# DSO_CPLD.net
KiCad netlist of a schematic drawn in Altium Designer
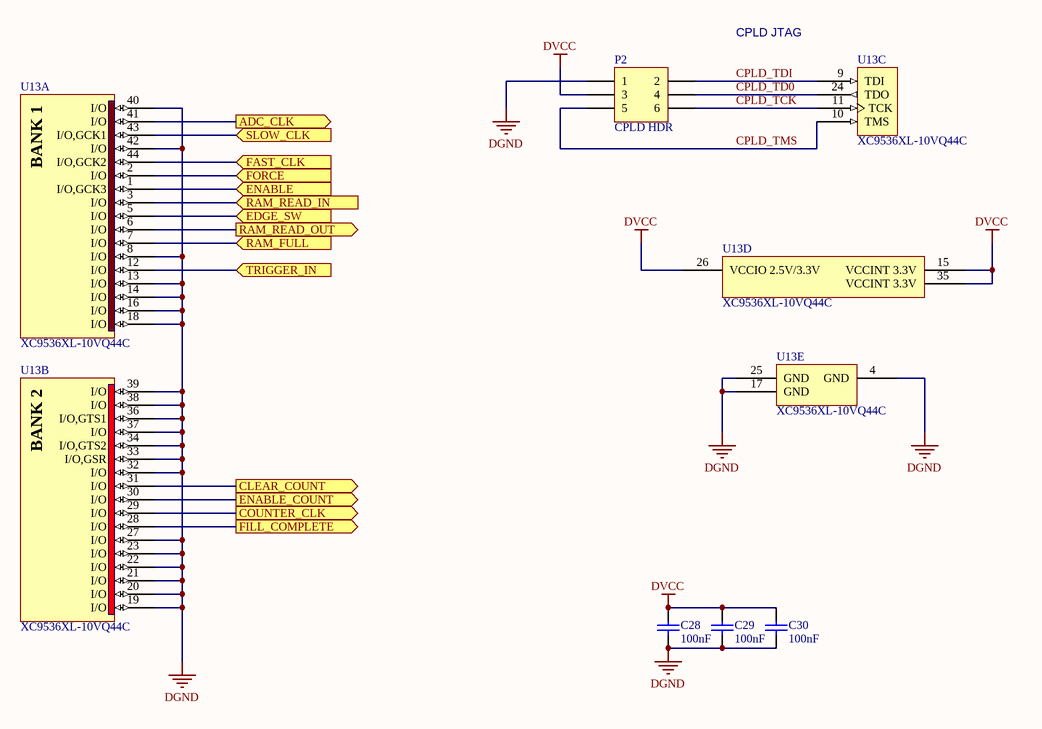
[diagram p0: DSO_CPLD.SchDoc]

(export (version "E")
  (design (tool "Eeschema 10.0.6"))
  (components
    (comp (ref "C28")
      (value "100nF")
      (footprint "0805C")
      (description "Capacitor")
      (fields (field (name "REVIEWED BY") "RM - 2018/08/05"))
      (libsource (lib "DSO") (part "C"))
    )
    (comp (ref "C29")
      (value "100nF")
      (footprint "0805C")
      (description "Capacitor")
      (fields (field (name "REVIEWED BY") "RM - 2018/08/05"))
      (libsource (lib "DSO") (part "C"))
    )
    (comp (ref "C30")
      (value "100nF")
      (footprint "0805C")
      (description "Capacitor")
      (fields (field (name "REVIEWED BY") "RM - 2018/08/05"))
      (libsource (lib "DSO") (part "C"))
    )
    (comp (ref "P2")
      (value "CPLD HDR")
      (footprint "HDR3x2")
      (description "Header, 5-Pin")
      (fields (field (name "REVIEWED BY") "RM - 2018/08/05"))
      (libsource (lib "DSO") (part "Header 3x2"))
    )
    (comp (ref "U13")
      (value "XC9536XL-10VQ44C")
      (footprint "VQ44_L")
      (fields (field (name "REVIEWED BY") "RM - 2018/08/05"))
      (libsource (lib "DSO") (part "XC9536XL-10VQG44C"))
    )
  )
  (nets
    (net (code "1") (name "/ADC_CLK") (class "Default")
      (node (ref "U13") (pin "41") (pinfunction "I/O_41") (pintype "bidirectional"))
    )
    (net (code "2") (name "/CLEAR_COUNT") (class "Default")
      (node (ref "U13") (pin "31") (pinfunction "I/O_31") (pintype "bidirectional"))
    )
    (net (code "3") (name "/COUNTER_CLK") (class "Default")
      (node (ref "U13") (pin "29") (pinfunction "I/O_29") (pintype "bidirectional"))
    )
    (net (code "4") (name "/CPLD_TCK") (class "Default")
      (node (ref "P2") (pin "6") (pinfunction "6_6") (pintype "passive"))
      (node (ref "U13") (pin "11") (pinfunction "TCK_11") (pintype "input"))
    )
    (net (code "5") (name "/CPLD_TD0") (class "Default")
      (node (ref "P2") (pin "4") (pinfunction "4_4") (pintype "passive"))
      (node (ref "U13") (pin "24") (pinfunction "TDO_24") (pintype "output"))
    )
    (net (code "6") (name "/CPLD_TDI") (class "Default")
      (node (ref "P2") (pin "2") (pinfunction "2_2") (pintype "passive"))
      (node (ref "U13") (pin "9") (pinfunction "TDI_9") (pintype "input"))
    )
    (net (code "7") (name "/CPLD_TMS") (class "Default")
      (node (ref "P2") (pin "5") (pinfunction "5_5") (pintype "passive"))
      (node (ref "U13") (pin "10") (pinfunction "TMS_10") (pintype "input"))
    )
    (net (code "8") (name "/EDGE_SW") (class "Default")
      (node (ref "U13") (pin "5") (pinfunction "I/O_5") (pintype "bidirectional"))
    )
    (net (code "9") (name "/ENABLE") (class "Default")
      (node (ref "U13") (pin "1") (pinfunction "I/O,GCK3_1") (pintype "bidirectional"))
    )
    (net (code "10") (name "/ENABLE_COUNT") (class "Default")
      (node (ref "U13") (pin "30") (pinfunction "I/O_30") (pintype "bidirectional"))
    )
    (net (code "11") (name "/FAST_CLK") (class "Default")
      (node (ref "U13") (pin "44") (pinfunction "I/O,GCK2_44") (pintype "bidirectional"))
    )
    (net (code "12") (name "/FILL_COMPLETE") (class "Default")
      (node (ref "U13") (pin "28") (pinfunction "I/O_28") (pintype "bidirectional"))
    )
    (net (code "13") (name "/FORCE") (class "Default")
      (node (ref "U13") (pin "2") (pinfunction "I/O_2") (pintype "bidirectional"))
    )
    (net (code "14") (name "/RAM_FULL") (class "Default")
      (node (ref "U13") (pin "7") (pinfunction "I/O_7") (pintype "bidirectional"))
    )
    (net (code "15") (name "/RAM_READ_IN") (class "Default")
      (node (ref "U13") (pin "3") (pinfunction "I/O_3") (pintype "bidirectional"))
    )
    (net (code "16") (name "/RAM_READ_OUT") (class "Default")
      (node (ref "U13") (pin "6") (pinfunction "I/O_6") (pintype "bidirectional"))
    )
    (net (code "17") (name "/SLOW_CLK") (class "Default")
      (node (ref "U13") (pin "43") (pinfunction "I/O,GCK1_43") (pintype "bidirectional"))
    )
    (net (code "18") (name "/TRIGGER_IN") (class "Default")
      (node (ref "U13") (pin "12") (pinfunction "I/O_12") (pintype "bidirectional"))
    )
    (net (code "19") (name "DGND") (class "Default")
      (node (ref "C28") (pin "2") (pinfunction "2_2") (pintype "passive"))
      (node (ref "C29") (pin "2") (pinfunction "2_2") (pintype "passive"))
      (node (ref "C30") (pin "2") (pinfunction "2_2") (pintype "passive"))
      (node (ref "P2") (pin "1") (pinfunction "1_1") (pintype "passive"))
      (node (ref "U13") (pin "13") (pinfunction "I/O_13") (pintype "bidirectional"))
      (node (ref "U13") (pin "14") (pinfunction "I/O_14") (pintype "bidirectional"))
      (node (ref "U13") (pin "16") (pinfunction "I/O_16") (pintype "bidirectional"))
      (node (ref "U13") (pin "17") (pinfunction "GND_17") (pintype "power_in"))
      (node (ref "U13") (pin "18") (pinfunction "I/O_18") (pintype "bidirectional"))
      (node (ref "U13") (pin "19") (pinfunction "I/O_19") (pintype "bidirectional"))
      (node (ref "U13") (pin "20") (pinfunction "I/O_20") (pintype "bidirectional"))
      (node (ref "U13") (pin "21") (pinfunction "I/O_21") (pintype "bidirectional"))
      (node (ref "U13") (pin "22") (pinfunction "I/O_22") (pintype "bidirectional"))
      (node (ref "U13") (pin "23") (pinfunction "I/O_23") (pintype "bidirectional"))
      (node (ref "U13") (pin "25") (pinfunction "GND_25") (pintype "power_in"))
      (node (ref "U13") (pin "27") (pinfunction "I/O_27") (pintype "bidirectional"))
      (node (ref "U13") (pin "32") (pinfunction "I/O_32") (pintype "bidirectional"))
      (node (ref "U13") (pin "33") (pinfunction "I/O,GSR_33") (pintype "bidirectional"))
      (node (ref "U13") (pin "34") (pinfunction "I/O,GTS2_34") (pintype "bidirectional"))
      (node (ref "U13") (pin "36") (pinfunction "I/O,GTS1_36") (pintype "bidirectional"))
      (node (ref "U13") (pin "37") (pinfunction "I/O_37") (pintype "bidirectional"))
      (node (ref "U13") (pin "38") (pinfunction "I/O_38") (pintype "bidirectional"))
      (node (ref "U13") (pin "39") (pinfunction "I/O_39") (pintype "bidirectional"))
      (node (ref "U13") (pin "4") (pinfunction "GND_4") (pintype "power_in"))
      (node (ref "U13") (pin "40") (pinfunction "I/O_40") (pintype "bidirectional"))
      (node (ref "U13") (pin "42") (pinfunction "I/O_42") (pintype "bidirectional"))
      (node (ref "U13") (pin "8") (pinfunction "I/O_8") (pintype "bidirectional"))
    )
    (net (code "20") (name "DVCC") (class "Default")
      (node (ref "C28") (pin "1") (pinfunction "1_1") (pintype "passive"))
      (node (ref "C29") (pin "1") (pinfunction "1_1") (pintype "passive"))
      (node (ref "C30") (pin "1") (pinfunction "1_1") (pintype "passive"))
      (node (ref "P2") (pin "3") (pinfunction "3_3") (pintype "passive"))
      (node (ref "U13") (pin "15") (pinfunction "VCCINT_3.3V_15") (pintype "power_in"))
      (node (ref "U13") (pin "26") (pinfunction "VCCIO_2.5V/3.3V_26") (pintype "power_in"))
      (node (ref "U13") (pin "35") (pinfunction "VCCINT_3.3V_35") (pintype "power_in"))
    )
  )
)
